# IO.net
KiCad netlist of a schematic drawn in Altium Designer
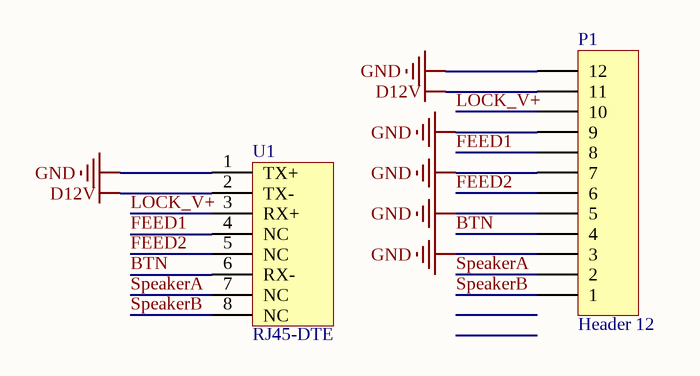
[diagram p0: IO.SchDoc]

(export (version "E")
  (design (tool "Eeschema 10.0.6"))
  (components
    (comp (ref "P1")
      (value "Header 12")
      (footprint "KF128-3.81-12")
      (description "Header, 12-Pin")
      (fields (field (name "PUBLISHER") "Altium Limited"))
      (libsource (lib "lib_AD") (part "Header 12"))
    )
    (comp (ref "U1") (value "RJ45-DTE") (footprint "RJ45") (libsource (lib "lib_AD") (part "RJ45-DTE")))
  )
  (nets
    (net (code "1") (name "/BTN") (class "Default")
      (node (ref "P1") (pin "4") (pinfunction "4_4") (pintype "passive"))
      (node (ref "U1") (pin "6") (pinfunction "RX-_6") (pintype "passive"))
    )
    (net (code "2") (name "/FEED1") (class "Default")
      (node (ref "P1") (pin "8") (pinfunction "8_8") (pintype "passive"))
      (node (ref "U1") (pin "4") (pinfunction "NC_4") (pintype "passive"))
    )
    (net (code "3") (name "/FEED2") (class "Default")
      (node (ref "P1") (pin "6") (pinfunction "6_6") (pintype "passive"))
      (node (ref "U1") (pin "5") (pinfunction "NC_5") (pintype "passive"))
    )
    (net (code "4") (name "/LOCK_V+") (class "Default")
      (node (ref "P1") (pin "10") (pinfunction "10_10") (pintype "passive"))
      (node (ref "U1") (pin "3") (pinfunction "RX+_3") (pintype "passive"))
    )
    (net (code "5") (name "/SpeakerA") (class "Default")
      (node (ref "P1") (pin "2") (pinfunction "2_2") (pintype "passive"))
      (node (ref "U1") (pin "7") (pinfunction "NC_7") (pintype "passive"))
    )
    (net (code "6") (name "/SpeakerB") (class "Default")
      (node (ref "P1") (pin "1") (pinfunction "1_1") (pintype "passive"))
      (node (ref "U1") (pin "8") (pinfunction "NC_8") (pintype "passive"))
    )
    (net (code "7") (name "D12V") (class "Default")
      (node (ref "P1") (pin "11") (pinfunction "11_11") (pintype "passive"))
      (node (ref "U1") (pin "2") (pinfunction "TX-_2") (pintype "passive"))
    )
    (net (code "8") (name "GND") (class "Default")
      (node (ref "P1") (pin "12") (pinfunction "12_12") (pintype "passive"))
      (node (ref "P1") (pin "3") (pinfunction "3_3") (pintype "passive"))
      (node (ref "P1") (pin "5") (pinfunction "5_5") (pintype "passive"))
      (node (ref "P1") (pin "7") (pinfunction "7_7") (pintype "passive"))
      (node (ref "P1") (pin "9") (pinfunction "9_9") (pintype "passive"))
      (node (ref "U1") (pin "1") (pinfunction "TX+_1") (pintype "passive"))
    )
  )
)
